# Main_Schematic.net
KiCad netlist of a schematic drawn in Altium Designer
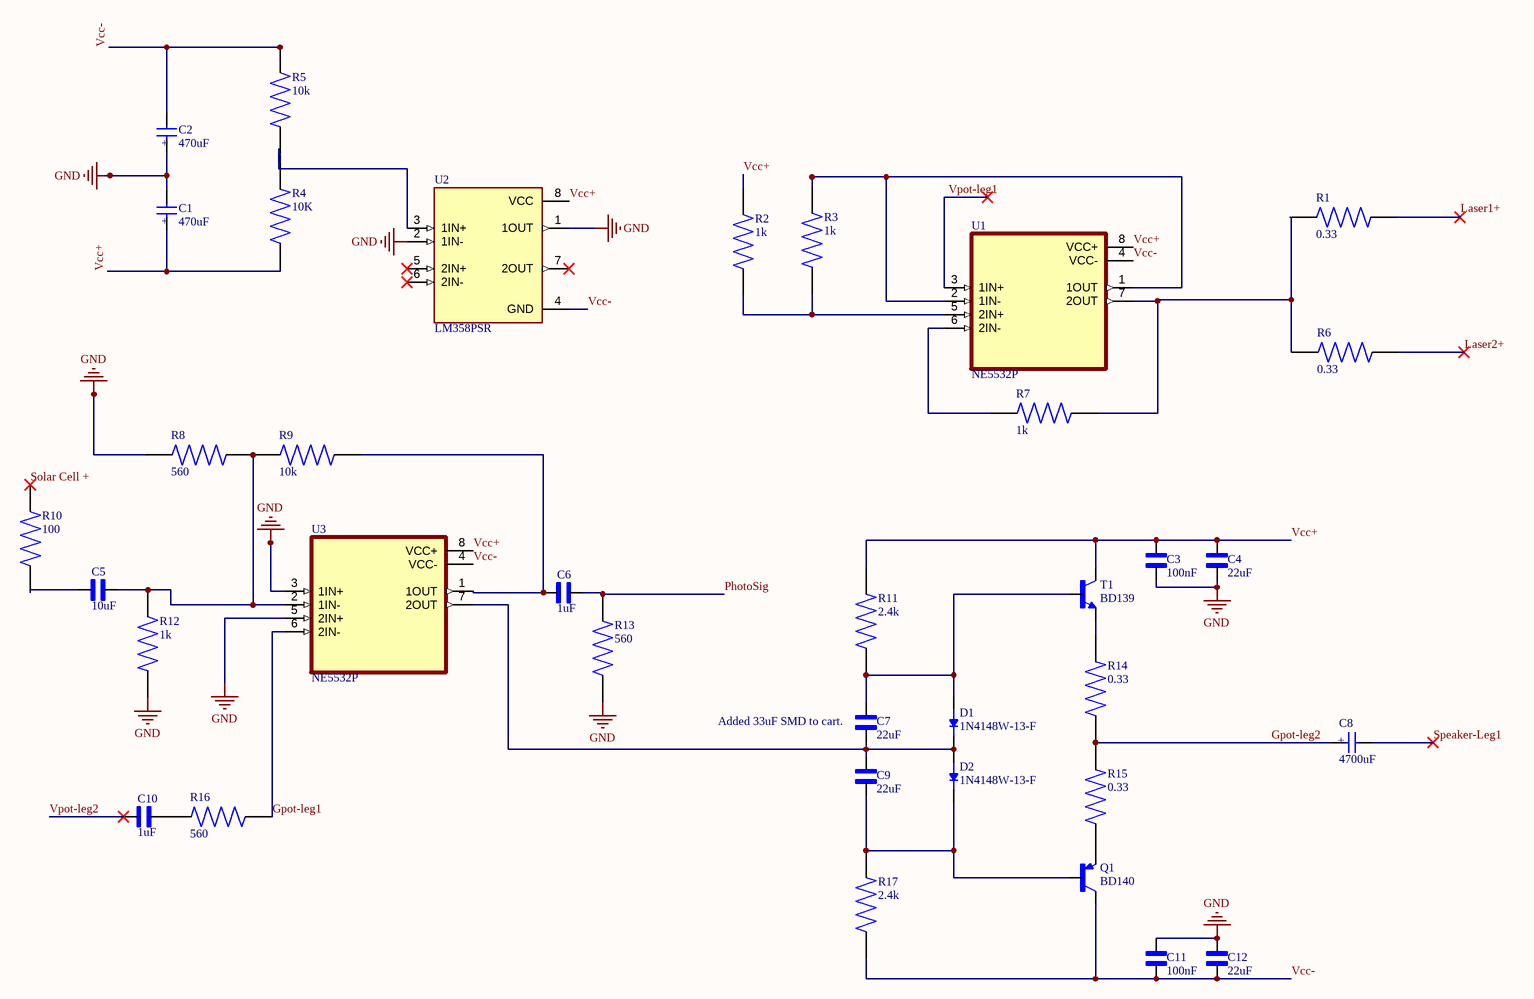
[diagram p0: Main_Schematic.SchDoc]

(export (version "E")
  (design (tool "Eeschema 10.0.6"))
  (components
    (comp (ref "C1")
      (value "470uF")
      (footprint "WCAP-ATG8_5X11(DXL)")
      (description "CAP ALUM 33UF 20% 35V RADIAL TH")
      (fields (field (name "MP") "860010572004") (field (name "MF") "WÃ¼rth Elektronik"))
      (libsource (lib "Josh Ginnett") (part "WCAP-ATG8_5X11"))
    )
    (comp (ref "C2")
      (value "470uF")
      (footprint "WCAP-ATG8_5X11(DXL)")
      (description "CAP ALUM 33UF 20% 35V RADIAL TH")
      (fields (field (name "MP") "860010572004") (field (name "MF") "WÃ¼rth Elektronik"))
      (libsource (lib "Josh Ginnett") (part "WCAP-ATG8_5X11"))
    )
    (comp (ref "C3")
      (value "100nF")
      (footprint "CAPC3216X180N")
      (description "CL31 Series 10 uF 25 V Â±10 % Tolerance X7R SMT Multilayer Ceramic Capacitor")
      (fields (field (name "MF") "Samsung Electro-Mechanics") (field (name "MP") "CL31B106KAHNNNE"))
      (libsource (lib "Josh Ginnett") (part "CL31B106KAHNNNE"))
    )
    (comp (ref "C4")
      (value "22uF")
      (footprint "CAPC3216X180N")
      (description "CL31 Series 10 uF 25 V Â±10 % Tolerance X7R SMT Multilayer Ceramic Capacitor")
      (fields (field (name "MF") "Samsung Electro-Mechanics") (field (name "MP") "CL31B106KAHNNNE"))
      (libsource (lib "Josh Ginnett") (part "CL31B106KAHNNNE"))
    )
    (comp (ref "C5")
      (value "10uF")
      (footprint "CAPC3216X180N")
      (description "CL31 Series 10 uF 25 V Â±10 % Tolerance X7R SMT Multilayer Ceramic Capacitor")
      (fields (field (name "MF") "Samsung Electro-Mechanics") (field (name "MP") "CL31B106KAHNNNE"))
      (libsource (lib "") (part "CL31B106KAHNNNE_1"))
    )
    (comp (ref "C6")
      (value "1uF")
      (footprint "CAPC3216X180N")
      (description "CL31 Series 10 uF 25 V Â±10 % Tolerance X7R SMT Multilayer Ceramic Capacitor")
      (fields (field (name "MF") "Samsung Electro-Mechanics") (field (name "MP") "CL31B106KAHNNNE"))
      (libsource (lib "") (part "CL31B106KAHNNNE_1"))
    )
    (comp (ref "C7")
      (value "22uF")
      (footprint "CAPC3216X180N")
      (description "CL31 Series 10 uF 25 V Â±10 % Tolerance X7R SMT Multilayer Ceramic Capacitor")
      (fields (field (name "MF") "Samsung Electro-Mechanics") (field (name "MP") "CL31B106KAHNNNE"))
      (libsource (lib "Josh Ginnett") (part "CL31B106KAHNNNE"))
    )
    (comp (ref "C8")
      (value "4700uF")
      (footprint "WCAP-ATG8_5X11(DXL)")
      (description "CAP ALUM 33UF 20% 35V RADIAL TH")
      (fields (field (name "MP") "860010572004") (field (name "MF") "WÃ¼rth Elektronik"))
      (libsource (lib "Josh Ginnett") (part "WCAP-ATG8_5X11"))
    )
    (comp (ref "C9")
      (value "22uF")
      (footprint "CAPC3216X180N")
      (description "CL31 Series 10 uF 25 V Â±10 % Tolerance X7R SMT Multilayer Ceramic Capacitor")
      (fields (field (name "MF") "Samsung Electro-Mechanics") (field (name "MP") "CL31B106KAHNNNE"))
      (libsource (lib "Josh Ginnett") (part "CL31B106KAHNNNE"))
    )
    (comp (ref "C10")
      (value "1uF")
      (footprint "CAPC3216X180N")
      (description "CL31 Series 10 uF 25 V Â±10 % Tolerance X7R SMT Multilayer Ceramic Capacitor")
      (fields (field (name "MF") "Samsung Electro-Mechanics") (field (name "MP") "CL31B106KAHNNNE"))
      (libsource (lib "") (part "CL31B106KAHNNNE_1"))
    )
    (comp (ref "C11")
      (value "100nF")
      (footprint "CAPC3216X180N")
      (description "CL31 Series 10 uF 25 V Â±10 % Tolerance X7R SMT Multilayer Ceramic Capacitor")
      (fields (field (name "MF") "Samsung Electro-Mechanics") (field (name "MP") "CL31B106KAHNNNE"))
      (libsource (lib "Josh Ginnett") (part "CL31B106KAHNNNE"))
    )
    (comp (ref "C12")
      (value "22uF")
      (footprint "CAPC3216X180N")
      (description "CL31 Series 10 uF 25 V Â±10 % Tolerance X7R SMT Multilayer Ceramic Capacitor")
      (fields (field (name "MF") "Samsung Electro-Mechanics") (field (name "MP") "CL31B106KAHNNNE"))
      (libsource (lib "Josh Ginnett") (part "CL31B106KAHNNNE"))
    )
    (comp (ref "D1")
      (value "1N4148W-13-F")
      (footprint "SOD3715X135N")
      (description "Diode Switching 100V 0.15A 2Pin SOD123")
      (fields (field (name "MF") "Diodes Inc."))
      (libsource (lib "Josh Ginnett") (part "1N4148W-13-F"))
    )
    (comp (ref "D2")
      (value "1N4148W-13-F")
      (footprint "SOD3715X135N")
      (description "Diode Switching 100V 0.15A 2Pin SOD123")
      (fields (field (name "MF") "Diodes Inc."))
      (libsource (lib "Josh Ginnett") (part "1N4148W-13-F"))
    )
    (comp (ref "Q1")
      (value "BD140")
      (footprint "BD139- TO Model")
      (description "Bipolar (BJT) Transistor PNP 80 V 1.5 A - 1.25 W Through Hole TO-126-3")
      (fields (field (name "MF") "ON Semiconductor"))
      (libsource (lib "Josh Ginnett") (part "BD140"))
    )
    (comp (ref "R1")
      (value "0.33")
      (footprint "RESAD1100W55L680D260")
      (description "10.5 kOhms Â±1% 0.25W, 1/4W Through Hole Resistor Axial - Metal Film")
      (fields (field (name "MF") "Yageo") (field (name "MP") "MFR-25FRF52-10K5"))
      (libsource (lib "Josh Ginnett") (part "MFR-25FRF52-10K5"))
    )
    (comp (ref "R2")
      (value "1k")
      (footprint "RESC3216X70N")
      (description "0 Ohms Jumper 0.25W, 1/4W Chip Resistor 1206 (3216 Metric) Automotive AEC-Q200 Thick Film")
      (fields (field (name "MP") "RMCF1206ZT0R00") (field (name "MF") "Stackpole Electronics Inc"))
      (libsource (lib "Josh Ginnett") (part "RMCF1206ZT0R00"))
    )
    (comp (ref "R3")
      (value "1k")
      (footprint "RESC3216X70N")
      (description "0 Ohms Jumper 0.25W, 1/4W Chip Resistor 1206 (3216 Metric) Automotive AEC-Q200 Thick Film")
      (fields (field (name "MP") "RMCF1206ZT0R00") (field (name "MF") "Stackpole Electronics Inc"))
      (libsource (lib "Josh Ginnett") (part "RMCF1206ZT0R00"))
    )
    (comp (ref "R4")
      (value "10K")
      (footprint "RESC3216X70N")
      (description "0 Ohms Jumper 0.25W, 1/4W Chip Resistor 1206 (3216 Metric) Automotive AEC-Q200 Thick Film")
      (fields (field (name "MP") "RMCF1206ZT0R00") (field (name "MF") "Stackpole Electronics Inc"))
      (libsource (lib "Josh Ginnett") (part "RMCF1206ZT0R00"))
    )
    (comp (ref "R5")
      (value "10k")
      (footprint "RESC3216X70N")
      (description "0 Ohms Jumper 0.25W, 1/4W Chip Resistor 1206 (3216 Metric) Automotive AEC-Q200 Thick Film")
      (fields (field (name "MP") "RMCF1206ZT0R00") (field (name "MF") "Stackpole Electronics Inc"))
      (libsource (lib "Josh Ginnett") (part "RMCF1206ZT0R00"))
    )
    (comp (ref "R6")
      (value "0.33")
      (footprint "RESAD1100W55L680D260")
      (description "10.5 kOhms Â±1% 0.25W, 1/4W Through Hole Resistor Axial - Metal Film")
      (fields (field (name "MF") "Yageo") (field (name "MP") "MFR-25FRF52-10K5"))
      (libsource (lib "Josh Ginnett") (part "MFR-25FRF52-10K5"))
    )
    (comp (ref "R7")
      (value "1k")
      (footprint "RESC3216X70N")
      (description "0 Ohms Jumper 0.25W, 1/4W Chip Resistor 1206 (3216 Metric) Automotive AEC-Q200 Thick Film")
      (fields (field (name "MP") "RMCF1206ZT0R00") (field (name "MF") "Stackpole Electronics Inc"))
      (libsource (lib "Josh Ginnett") (part "RMCF1206ZT0R00"))
    )
    (comp (ref "R8")
      (value "560")
      (footprint "RESC3216X70N")
      (description "0 Ohms Jumper 0.25W, 1/4W Chip Resistor 1206 (3216 Metric) Automotive AEC-Q200 Thick Film")
      (fields (field (name "MP") "RMCF1206ZT0R00") (field (name "MF") "Stackpole Electronics Inc"))
      (libsource (lib "Josh Ginnett") (part "RMCF1206ZT0R00"))
    )
    (comp (ref "R9")
      (value "10k")
      (footprint "RESC3216X70N")
      (description "0 Ohms Jumper 0.25W, 1/4W Chip Resistor 1206 (3216 Metric) Automotive AEC-Q200 Thick Film")
      (fields (field (name "MP") "RMCF1206ZT0R00") (field (name "MF") "Stackpole Electronics Inc"))
      (libsource (lib "Josh Ginnett") (part "RMCF1206ZT0R00"))
    )
    (comp (ref "R10")
      (value "100")
      (footprint "RESC3216X70N")
      (description "0 Ohms Jumper 0.25W, 1/4W Chip Resistor 1206 (3216 Metric) Automotive AEC-Q200 Thick Film")
      (fields (field (name "MP") "RMCF1206ZT0R00") (field (name "MF") "Stackpole Electronics Inc"))
      (libsource (lib "Josh Ginnett") (part "RMCF1206ZT0R00"))
    )
    (comp (ref "R11")
      (value "2.4k")
      (footprint "RESC3216X70N")
      (description "0 Ohms Jumper 0.25W, 1/4W Chip Resistor 1206 (3216 Metric) Automotive AEC-Q200 Thick Film")
      (fields (field (name "MP") "RMCF1206ZT0R00") (field (name "MF") "Stackpole Electronics Inc"))
      (libsource (lib "Josh Ginnett") (part "RMCF1206ZT0R00"))
    )
    (comp (ref "R12")
      (value "1k")
      (footprint "RESC3216X70N")
      (description "0 Ohms Jumper 0.25W, 1/4W Chip Resistor 1206 (3216 Metric) Automotive AEC-Q200 Thick Film")
      (fields (field (name "MP") "RMCF1206ZT0R00") (field (name "MF") "Stackpole Electronics Inc"))
      (libsource (lib "Josh Ginnett") (part "RMCF1206ZT0R00"))
    )
    (comp (ref "R13")
      (value "560")
      (footprint "RESC3216X70N")
      (description "0 Ohms Jumper 0.25W, 1/4W Chip Resistor 1206 (3216 Metric) Automotive AEC-Q200 Thick Film")
      (fields (field (name "MP") "RMCF1206ZT0R00") (field (name "MF") "Stackpole Electronics Inc"))
      (libsource (lib "Josh Ginnett") (part "RMCF1206ZT0R00"))
    )
    (comp (ref "R14")
      (value "0.33")
      (footprint "RESAD1100W55L680D260")
      (description "10.5 kOhms Â±1% 0.25W, 1/4W Through Hole Resistor Axial - Metal Film")
      (fields (field (name "MF") "Yageo") (field (name "MP") "MFR-25FRF52-10K5"))
      (libsource (lib "Josh Ginnett") (part "MFR-25FRF52-10K5"))
    )
    (comp (ref "R15")
      (value "0.33")
      (footprint "RESAD1100W55L680D260")
      (description "10.5 kOhms Â±1% 0.25W, 1/4W Through Hole Resistor Axial - Metal Film")
      (fields (field (name "MF") "Yageo") (field (name "MP") "MFR-25FRF52-10K5"))
      (libsource (lib "Josh Ginnett") (part "MFR-25FRF52-10K5"))
    )
    (comp (ref "R16")
      (value "560")
      (footprint "RESC3216X70N")
      (description "0 Ohms Jumper 0.25W, 1/4W Chip Resistor 1206 (3216 Metric) Automotive AEC-Q200 Thick Film")
      (fields (field (name "MP") "RMCF1206ZT0R00") (field (name "MF") "Stackpole Electronics Inc"))
      (libsource (lib "Josh Ginnett") (part "RMCF1206ZT0R00"))
    )
    (comp (ref "R17")
      (value "2.4k")
      (footprint "RESC3216X70N")
      (description "0 Ohms Jumper 0.25W, 1/4W Chip Resistor 1206 (3216 Metric) Automotive AEC-Q200 Thick Film")
      (fields (field (name "MP") "RMCF1206ZT0R00") (field (name "MF") "Stackpole Electronics Inc"))
      (libsource (lib "Josh Ginnett") (part "RMCF1206ZT0R00"))
    )
    (comp (ref "T1")
      (value "BD139")
      (footprint "BD139-TO")
      (description "Bipolar (BJT) Transistor NPN 80 V 1.5 A - 1.25 W Through Hole TO-126-3")
      (fields (field (name "MF") "ON"))
      (libsource (lib "Josh Ginnett") (part "BD139"))
    )
    (comp (ref "U1")
      (value "NE5532P")
      (footprint "DIP794W45P254L959H508Q8")
      (description "Dual, 30-V, 10-MHz, low-noise operational amplifier for audio applications")
      (fields (field (name "MF") "Texas Instruments"))
      (libsource (lib "Josh Ginnett") (part "NE5532P"))
    )
    (comp (ref "U2")
      (value "LM358PSR")
      (footprint "SOIC127P780X200-8N")
      (description "Dual, 30-V, 700-kHz operational amplifier")
      (fields (field (name "MF") "Texas Instruments"))
      (libsource (lib "Josh Ginnett") (part "LM358PSR"))
    )
    (comp (ref "U3")
      (value "NE5532P")
      (footprint "DIP794W45P254L959H508Q8")
      (description "Dual, 30-V, 10-MHz, low-noise operational amplifier for audio applications")
      (fields (field (name "MF") "Texas Instruments"))
      (libsource (lib "Josh Ginnett") (part "NE5532P"))
    )
  )
  (nets
    (net (code "1") (name "/Gpot-leg1") (class "Default")
      (node (ref "R16") (pin "2") (pinfunction "2_2") (pintype "passive"))
      (node (ref "U3") (pin "6") (pinfunction "2IN-_6") (pintype "input"))
    )
    (net (code "2") (name "/Gpot-leg2") (class "Default")
      (node (ref "C8") (pin "1") (pinfunction "POS_1") (pintype "passive"))
      (node (ref "R14") (pin "1") (pinfunction "1_1") (pintype "passive"))
      (node (ref "R15") (pin "2") (pinfunction "2_2") (pintype "passive"))
    )
    (net (code "3") (name "/Laser1+") (class "Default")
      (node (ref "R1") (pin "1") (pinfunction "1_1") (pintype "passive+no_connect"))
    )
    (net (code "4") (name "/Laser2+") (class "Default")
      (node (ref "R6") (pin "1") (pinfunction "1_1") (pintype "passive+no_connect"))
    )
    (net (code "5") (name "/PhotoSig") (class "Default")
      (node (ref "C6") (pin "2") (pinfunction "2_2") (pintype "passive"))
      (node (ref "R13") (pin "2") (pinfunction "2_2") (pintype "passive"))
    )
    (net (code "6") (name "/Solar Cell +") (class "Default")
      (node (ref "R10") (pin "1") (pinfunction "1_1") (pintype "passive+no_connect"))
    )
    (net (code "7") (name "/Speaker-Leg1") (class "Default")
      (node (ref "C8") (pin "2") (pinfunction "NEG_2") (pintype "passive+no_connect"))
    )
    (net (code "8") (name "/Vcc+") (class "Default")
      (node (ref "C1") (pin "1") (pinfunction "POS_1") (pintype "passive"))
      (node (ref "C3") (pin "2") (pinfunction "2_2") (pintype "passive"))
      (node (ref "C4") (pin "2") (pinfunction "2_2") (pintype "passive"))
      (node (ref "R11") (pin "2") (pinfunction "2_2") (pintype "passive"))
      (node (ref "R2") (pin "2") (pinfunction "2_2") (pintype "passive"))
      (node (ref "R4") (pin "2") (pinfunction "2_2") (pintype "passive"))
      (node (ref "T1") (pin "2") (pinfunction "C_2") (pintype "passive"))
      (node (ref "U1") (pin "8") (pinfunction "VCC+_8") (pintype "power_in"))
      (node (ref "U2") (pin "8") (pinfunction "VCC_8") (pintype "power_in"))
      (node (ref "U3") (pin "8") (pinfunction "VCC+_8") (pintype "power_in"))
    )
    (net (code "9") (name "/Vcc-") (class "Default")
      (node (ref "C11") (pin "1") (pinfunction "1_1") (pintype "passive"))
      (node (ref "C12") (pin "1") (pinfunction "1_1") (pintype "passive"))
      (node (ref "C2") (pin "2") (pinfunction "NEG_2") (pintype "passive"))
      (node (ref "Q1") (pin "2") (pinfunction "C_2") (pintype "passive"))
      (node (ref "R17") (pin "1") (pinfunction "1_1") (pintype "passive"))
      (node (ref "R5") (pin "1") (pinfunction "1_1") (pintype "passive"))
      (node (ref "U1") (pin "4") (pinfunction "VCC-_4") (pintype "power_in"))
      (node (ref "U2") (pin "4") (pinfunction "GND_4") (pintype "power_in"))
      (node (ref "U3") (pin "4") (pinfunction "VCC-_4") (pintype "power_in"))
    )
    (net (code "10") (name "/Vpot-leg1") (class "Default")
      (node (ref "U1") (pin "3") (pinfunction "1IN+_3") (pintype "input+no_connect"))
    )
    (net (code "11") (name "/Vpot-leg2") (class "Default")
      (node (ref "C10") (pin "1") (pinfunction "1_1") (pintype "passive+no_connect"))
    )
    (net (code "12") (name "GND") (class "Default")
      (node (ref "C1") (pin "2") (pinfunction "NEG_2") (pintype "passive"))
      (node (ref "C11") (pin "2") (pinfunction "2_2") (pintype "passive"))
      (node (ref "C12") (pin "2") (pinfunction "2_2") (pintype "passive"))
      (node (ref "C2") (pin "1") (pinfunction "POS_1") (pintype "passive"))
      (node (ref "C3") (pin "1") (pinfunction "1_1") (pintype "passive"))
      (node (ref "C4") (pin "1") (pinfunction "1_1") (pintype "passive"))
      (node (ref "R12") (pin "2") (pinfunction "2_2") (pintype "passive"))
      (node (ref "R13") (pin "1") (pinfunction "1_1") (pintype "passive"))
      (node (ref "R8") (pin "1") (pinfunction "1_1") (pintype "passive"))
      (node (ref "U2") (pin "1") (pinfunction "1OUT_1") (pintype "output"))
      (node (ref "U2") (pin "2") (pinfunction "1IN-_2") (pintype "input"))
      (node (ref "U3") (pin "3") (pinfunction "1IN+_3") (pintype "input"))
      (node (ref "U3") (pin "5") (pinfunction "2IN+_5") (pintype "input"))
    )
    (net (code "13") (name "Net-(C5-Pad1)") (class "Default")
      (node (ref "C5") (pin "1") (pinfunction "1_1") (pintype "passive"))
      (node (ref "R10") (pin "2") (pinfunction "2_2") (pintype "passive"))
    )
    (net (code "14") (name "Net-(C10-Pad2)") (class "Default")
      (node (ref "C10") (pin "2") (pinfunction "2_2") (pintype "passive"))
      (node (ref "R16") (pin "1") (pinfunction "1_1") (pintype "passive"))
    )
    (net (code "15") (name "Net-(D1-K)") (class "Default")
      (node (ref "C7") (pin "1") (pinfunction "1_1") (pintype "passive"))
      (node (ref "C9") (pin "2") (pinfunction "2_2") (pintype "passive"))
      (node (ref "D1") (pin "C") (pinfunction "K_C") (pintype "passive"))
      (node (ref "D2") (pin "A") (pinfunction "A_A") (pintype "passive"))
      (node (ref "U3") (pin "7") (pinfunction "2OUT_7") (pintype "output"))
    )
    (net (code "16") (name "Net-(D2-K)") (class "Default")
      (node (ref "C9") (pin "1") (pinfunction "1_1") (pintype "passive"))
      (node (ref "D2") (pin "C") (pinfunction "K_C") (pintype "passive"))
      (node (ref "Q1") (pin "3") (pinfunction "B_3") (pintype "passive"))
      (node (ref "R17") (pin "2") (pinfunction "2_2") (pintype "passive"))
    )
    (net (code "17") (name "Net-(Q1-E)") (class "Default")
      (node (ref "Q1") (pin "1") (pinfunction "E_1") (pintype "passive"))
      (node (ref "R15") (pin "1") (pinfunction "1_1") (pintype "passive"))
    )
    (net (code "18") (name "Net-(R4-Pad1)") (class "Default")
      (node (ref "R4") (pin "1") (pinfunction "1_1") (pintype "passive"))
      (node (ref "R5") (pin "2") (pinfunction "2_2") (pintype "passive"))
    )
    (net (code "19") (name "Net-(T1-B)") (class "Default")
      (node (ref "C7") (pin "2") (pinfunction "2_2") (pintype "passive"))
      (node (ref "D1") (pin "A") (pinfunction "A_A") (pintype "passive"))
      (node (ref "R11") (pin "1") (pinfunction "1_1") (pintype "passive"))
      (node (ref "T1") (pin "1") (pinfunction "B_1") (pintype "passive"))
    )
    (net (code "20") (name "Net-(T1-E)") (class "Default")
      (node (ref "R14") (pin "2") (pinfunction "2_2") (pintype "passive"))
      (node (ref "T1") (pin "3") (pinfunction "E_3") (pintype "passive"))
    )
    (net (code "21") (name "Net-(U1-1IN-)") (class "Default")
      (node (ref "R3") (pin "2") (pinfunction "2_2") (pintype "passive"))
      (node (ref "U1") (pin "1") (pinfunction "1OUT_1") (pintype "output"))
      (node (ref "U1") (pin "2") (pinfunction "1IN-_2") (pintype "input"))
    )
    (net (code "22") (name "Net-(U1-2IN+)") (class "Default")
      (node (ref "R2") (pin "1") (pinfunction "1_1") (pintype "passive"))
      (node (ref "R3") (pin "1") (pinfunction "1_1") (pintype "passive"))
      (node (ref "U1") (pin "5") (pinfunction "2IN+_5") (pintype "input"))
    )
    (net (code "23") (name "Net-(U1-2IN-)") (class "Default")
      (node (ref "R7") (pin "2") (pinfunction "2_2") (pintype "passive"))
      (node (ref "U1") (pin "6") (pinfunction "2IN-_6") (pintype "input"))
    )
    (net (code "24") (name "Net-(U1-2OUT)") (class "Default")
      (node (ref "R1") (pin "2") (pinfunction "2_2") (pintype "passive"))
      (node (ref "R6") (pin "2") (pinfunction "2_2") (pintype "passive"))
      (node (ref "R7") (pin "1") (pinfunction "1_1") (pintype "passive"))
      (node (ref "U1") (pin "7") (pinfunction "2OUT_7") (pintype "output"))
    )
    (net (code "25") (name "Net-(U3-1IN-)") (class "Default")
      (node (ref "C5") (pin "2") (pinfunction "2_2") (pintype "passive"))
      (node (ref "R12") (pin "1") (pinfunction "1_1") (pintype "passive"))
      (node (ref "R8") (pin "2") (pinfunction "2_2") (pintype "passive"))
      (node (ref "R9") (pin "1") (pinfunction "1_1") (pintype "passive"))
      (node (ref "U3") (pin "2") (pinfunction "1IN-_2") (pintype "input"))
    )
    (net (code "26") (name "Net-(U3-1OUT)") (class "Default")
      (node (ref "C6") (pin "1") (pinfunction "1_1") (pintype "passive"))
      (node (ref "R9") (pin "2") (pinfunction "2_2") (pintype "passive"))
      (node (ref "U3") (pin "1") (pinfunction "1OUT_1") (pintype "output"))
    )
    (net (code "27") (name "unconnected-(U2-1IN+-Pad3)") (class "Default")
      (node (ref "U2") (pin "3") (pinfunction "1IN+_3") (pintype "input"))
    )
    (net (code "28") (name "unconnected-(U2-2IN+-Pad5)") (class "Default")
      (node (ref "U2") (pin "5") (pinfunction "2IN+_5") (pintype "input+no_connect"))
    )
    (net (code "29") (name "unconnected-(U2-2IN--Pad6)") (class "Default")
      (node (ref "U2") (pin "6") (pinfunction "2IN-_6") (pintype "input+no_connect"))
    )
    (net (code "30") (name "unconnected-(U2-2OUT-Pad7)") (class "Default")
      (node (ref "U2") (pin "7") (pinfunction "2OUT_7") (pintype "output+no_connect"))
    )
  )
)
